# cnc-spindle-driver.net
KiCad netlist of a schematic drawn in EAGLE
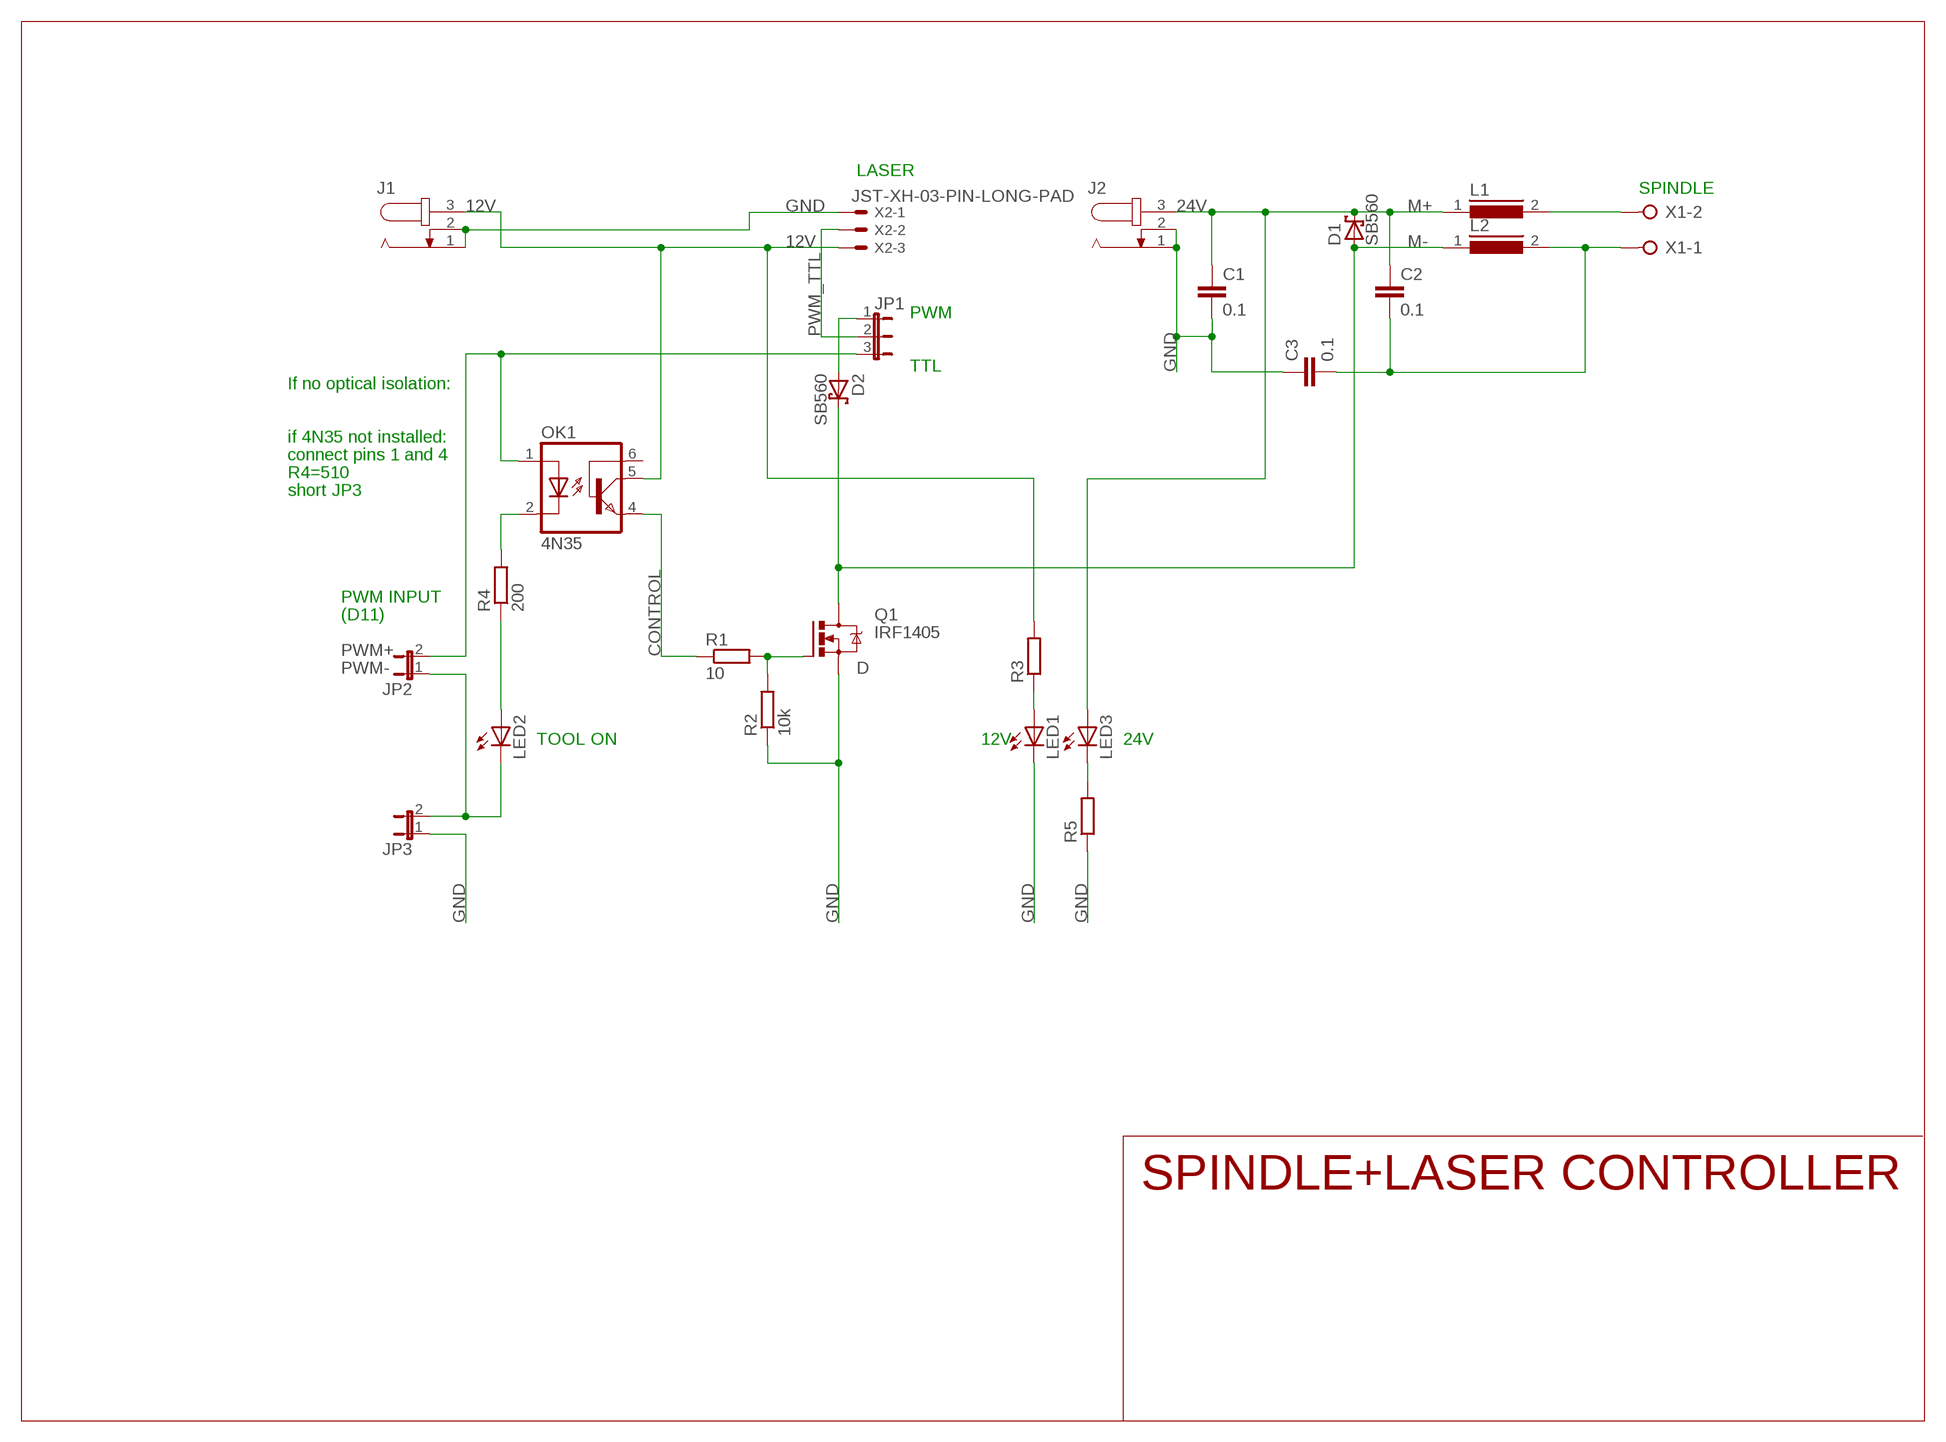
[diagram p0: schematic, sheet 1]

(export (version "E")
  (design (tool "Eeschema 10.0.6"))
  (components
    (comp (ref "C1")
      (value "0.1")
      (footprint "eagle-import:C025-025X050")
      (libsource (lib "eagle-import") (part "C-EU025-025X050"))
    )
    (comp (ref "C2")
      (value "0.1")
      (footprint "eagle-import:C025-025X050")
      (libsource (lib "eagle-import") (part "C-EU025-025X050"))
    )
    (comp (ref "C3")
      (value "0.1")
      (footprint "eagle-import:C025-025X050")
      (libsource (lib "eagle-import") (part "C-EU025-025X050"))
    )
    (comp (ref "D1")
      (value "SB560")
      (footprint "eagle-import:DO41-7.6")
      (libsource (lib "eagle-import") (part "1N5817-B"))
    )
    (comp (ref "D2")
      (value "SB560")
      (footprint "eagle-import:DO41-7.6")
      (libsource (lib "eagle-import") (part "1N5817-B"))
    )
    (comp (ref "J1")
      (value "JACK-PLUG0")
      (footprint "eagle-import:SPC4077")
      (libsource (lib "eagle-import") (part "JACK-PLUG0"))
    )
    (comp (ref "J2")
      (value "JACK-PLUG0")
      (footprint "eagle-import:SPC4077")
      (libsource (lib "eagle-import") (part "JACK-PLUG0"))
    )
    (comp (ref "JP1")
      (value "JP2E")
      (footprint "eagle-import:JP2")
      (libsource (lib "eagle-import") (part "JP2E"))
    )
    (comp (ref "JP2")
      (value "JP1E")
      (footprint "eagle-import:JP1")
      (libsource (lib "eagle-import") (part "JP1E"))
    )
    (comp (ref "JP3")
      (value "JP1E")
      (footprint "eagle-import:JP1")
      (libsource (lib "eagle-import") (part "JP1E"))
    )
    (comp (ref "L1")
      (value "R1003FS11")
      (footprint "eagle-import:S11-10")
      (libsource (lib "eagle-import") (part "R1003FS11"))
    )
    (comp (ref "L2")
      (value "R1003FS11")
      (footprint "eagle-import:S11-10")
      (libsource (lib "eagle-import") (part "R1003FS11"))
    )
    (comp (ref "LED1")
      (value "LED5MM")
      (footprint "eagle-import:LED5MM")
      (libsource (lib "eagle-import") (part "LED5MM"))
    )
    (comp (ref "LED2")
      (value "LED5MM")
      (footprint "eagle-import:LED5MM")
      (libsource (lib "eagle-import") (part "LED5MM"))
    )
    (comp (ref "LED3")
      (value "LED5MM")
      (footprint "eagle-import:LED5MM")
      (libsource (lib "eagle-import") (part "LED5MM"))
    )
    (comp (ref "OK1")
      (value "4N35")
      (footprint "eagle-import:DIL06")
      (fields (field (name "MF") "FAIRCHILD SEMICONDUCTOR"))
      (libsource (lib "eagle-import") (part "4N35"))
    )
    (comp (ref "Q1")
      (value "IRF1405")
      (footprint "eagle-import:TO220BV")
      (libsource (lib "eagle-import") (part "IRF540"))
    )
    (comp (ref "R1")
      (value "10")
      (footprint "eagle-import:0207_10")
      (libsource (lib "eagle-import") (part "R-EU_0207/10"))
    )
    (comp (ref "R2")
      (value "10k")
      (footprint "eagle-import:0207_10")
      (libsource (lib "eagle-import") (part "R-EU_0207/10"))
    )
    (comp (ref "R3")
      (value "R-EU_0207/2V")
      (footprint "eagle-import:0207_2V")
      (libsource (lib "eagle-import") (part "R-EU_0207/2V"))
    )
    (comp (ref "R4")
      (value "200")
      (footprint "eagle-import:0207_10")
      (libsource (lib "eagle-import") (part "R-EU_0207/10"))
    )
    (comp (ref "R5")
      (value "R-EU_0207/2V")
      (footprint "eagle-import:0207_2V")
      (libsource (lib "eagle-import") (part "R-EU_0207/2V"))
    )
    (comp (ref "X1")
      (value "W237-02P")
      (footprint "eagle-import:W237-132")
      (libsource (lib "eagle-import") (part "W237-02P"))
    )
    (comp (ref "X2")
      (value "JST-XH-03-PIN-LONG-PAD")
      (footprint "eagle-import:JST-XH-03-PACKAGE-LONG-PAD")
      (libsource (lib "eagle-import") (part "JST-XH-03-PIN-LONG-PAD"))
    )
  )
  (nets
    (net (code "1") (name "/12V") (class "Default")
      (node (ref "J1") (pin "3") (pinfunction "3_3") (pintype "passive"))
      (node (ref "OK1") (pin "5") (pinfunction "COL_5") (pintype "passive"))
      (node (ref "R3") (pin "2") (pinfunction "2_2") (pintype "passive"))
      (node (ref "X2") (pin "3") (pinfunction "S_3") (pintype "passive"))
    )
    (net (code "2") (name "/24V") (class "Default")
      (node (ref "C1") (pin "1") (pinfunction "1_1") (pintype "passive"))
      (node (ref "C2") (pin "1") (pinfunction "1_1") (pintype "passive"))
      (node (ref "D1") (pin "C") (pinfunction "C_C") (pintype "passive"))
      (node (ref "J2") (pin "3") (pinfunction "3_3") (pintype "passive"))
      (node (ref "L1") (pin "1") (pinfunction "1_1") (pintype "passive"))
      (node (ref "LED3") (pin "A") (pinfunction "A_A") (pintype "passive"))
    )
    (net (code "3") (name "/CONTROL") (class "Default")
      (node (ref "OK1") (pin "4") (pinfunction "EMI_4") (pintype "passive"))
      (node (ref "R1") (pin "1") (pinfunction "1_1") (pintype "passive"))
    )
    (net (code "4") (name "/D") (class "Default")
      (node (ref "D1") (pin "A") (pinfunction "A_A") (pintype "passive"))
      (node (ref "D2") (pin "C") (pinfunction "C_C") (pintype "passive"))
      (node (ref "L2") (pin "1") (pinfunction "1_1") (pintype "passive"))
      (node (ref "Q1") (pin "D") (pinfunction "D_D") (pintype "passive"))
    )
    (net (code "5") (name "/GND") (class "Default")
      (node (ref "C1") (pin "2") (pinfunction "2_2") (pintype "passive"))
      (node (ref "C3") (pin "1") (pinfunction "1_1") (pintype "passive"))
      (node (ref "J1") (pin "1") (pinfunction "1_1") (pintype "passive"))
      (node (ref "J1") (pin "2") (pinfunction "2_2") (pintype "passive"))
      (node (ref "J2") (pin "1") (pinfunction "1_1") (pintype "passive"))
      (node (ref "J2") (pin "2") (pinfunction "2_2") (pintype "passive"))
      (node (ref "JP3") (pin "1") (pinfunction "1_1") (pintype "passive"))
      (node (ref "LED1") (pin "K") (pinfunction "C_K") (pintype "passive"))
      (node (ref "Q1") (pin "S") (pinfunction "S_S") (pintype "passive"))
      (node (ref "R2") (pin "1") (pinfunction "1_1") (pintype "passive"))
      (node (ref "R5") (pin "1") (pinfunction "1_1") (pintype "passive"))
      (node (ref "X2") (pin "1") (pinfunction "S_1") (pintype "passive"))
    )
    (net (code "6") (name "/M+") (class "Default")
      (node (ref "L1") (pin "2") (pinfunction "2_2") (pintype "passive"))
      (node (ref "X1") (pin "2") (pinfunction "KL_2") (pintype "passive"))
    )
    (net (code "7") (name "/M-") (class "Default")
      (node (ref "C2") (pin "2") (pinfunction "2_2") (pintype "passive"))
      (node (ref "C3") (pin "2") (pinfunction "2_2") (pintype "passive"))
      (node (ref "L2") (pin "2") (pinfunction "2_2") (pintype "passive"))
      (node (ref "X1") (pin "1") (pinfunction "KL_1") (pintype "passive"))
    )
    (net (code "8") (name "/PWM+") (class "Default")
      (node (ref "JP1") (pin "3") (pinfunction "3_3") (pintype "passive"))
      (node (ref "JP2") (pin "2") (pinfunction "2_2") (pintype "passive"))
      (node (ref "OK1") (pin "1") (pinfunction "A_1") (pintype "passive"))
    )
    (net (code "9") (name "/PWM-") (class "Default")
      (node (ref "JP2") (pin "1") (pinfunction "1_1") (pintype "passive"))
      (node (ref "JP3") (pin "2") (pinfunction "2_2") (pintype "passive"))
      (node (ref "LED2") (pin "K") (pinfunction "C_K") (pintype "passive"))
    )
    (net (code "10") (name "/PWM_TTL") (class "Default")
      (node (ref "JP1") (pin "2") (pinfunction "2_2") (pintype "passive"))
      (node (ref "X2") (pin "2") (pinfunction "S_2") (pintype "passive"))
    )
    (net (code "11") (name "Net-(D2-PadA)") (class "Default")
      (node (ref "D2") (pin "A") (pinfunction "A_A") (pintype "passive"))
      (node (ref "JP1") (pin "1") (pinfunction "1_1") (pintype "passive"))
    )
    (net (code "12") (name "Net-(LED1-PadA)") (class "Default")
      (node (ref "LED1") (pin "A") (pinfunction "A_A") (pintype "passive"))
      (node (ref "R3") (pin "1") (pinfunction "1_1") (pintype "passive"))
    )
    (net (code "13") (name "Net-(LED2-PadA)") (class "Default")
      (node (ref "LED2") (pin "A") (pinfunction "A_A") (pintype "passive"))
      (node (ref "R4") (pin "1") (pinfunction "1_1") (pintype "passive"))
    )
    (net (code "14") (name "Net-(LED3-C)") (class "Default")
      (node (ref "LED3") (pin "K") (pinfunction "C_K") (pintype "passive"))
      (node (ref "R5") (pin "2") (pinfunction "2_2") (pintype "passive"))
    )
    (net (code "15") (name "Net-(OK1-C)") (class "Default")
      (node (ref "OK1") (pin "2") (pinfunction "C_2") (pintype "passive"))
      (node (ref "R4") (pin "2") (pinfunction "2_2") (pintype "passive"))
    )
    (net (code "16") (name "Net-(Q1-PadG)") (class "Default")
      (node (ref "Q1") (pin "G") (pinfunction "G_G") (pintype "passive"))
      (node (ref "R1") (pin "2") (pinfunction "2_2") (pintype "passive"))
      (node (ref "R2") (pin "2") (pinfunction "2_2") (pintype "passive"))
    )
    (net (code "17") (name "unconnected-(OK1-BAS-Pad6)") (class "Default")
      (node (ref "OK1") (pin "6") (pinfunction "BAS_6") (pintype "passive"))
    )
  )
)
